# Power_section.net
KiCad netlist of a schematic drawn in Altium Designer
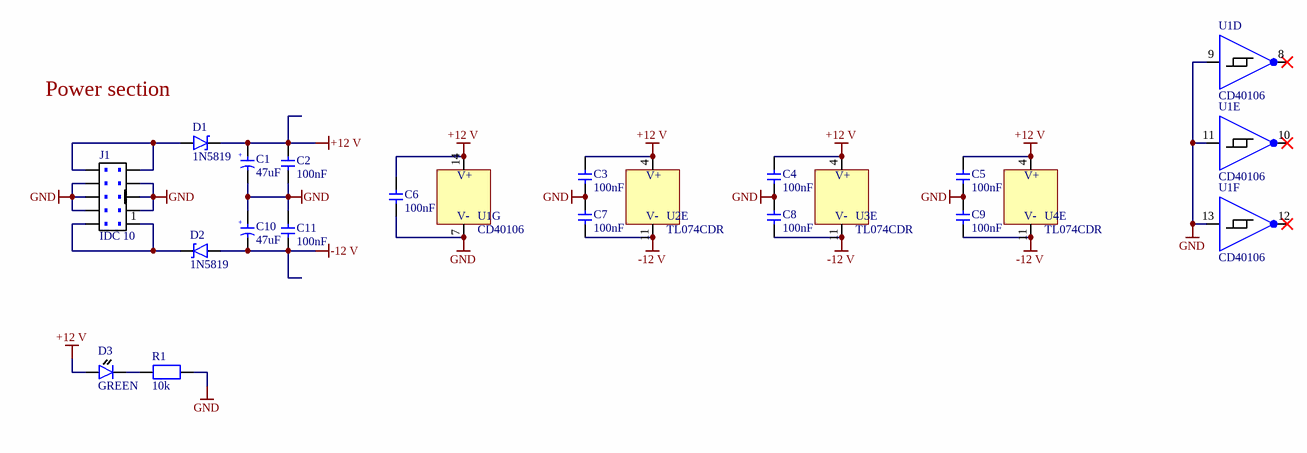
[diagram p0: Power section.SchDoc]

(export (version "E")
  (design (tool "Eeschema 10.0.6"))
  (components
    (comp (ref "C1")
      (value "47uF")
      (footprint "Cap electrolytic THT 5mm")
      (description "THT Electrolytic Capacitor 5 mm Diameter")
      (fields (field (name "Comment") "CAP"))
      (libsource (lib "Generic components") (part "Capacitor Electr THT 5mm"))
    )
    (comp (ref "C2")
      (value "100nF")
      (footprint "Cap SMD 0805")
      (description "SMD Capacitor Non-Polarised 0805 Package")
      (fields (field (name "Comment") "CAP"))
      (libsource (lib "Generic components") (part "Capacitor SMD 0805"))
    )
    (comp (ref "C3")
      (value "100nF")
      (footprint "Cap SMD 0805")
      (description "SMD Capacitor Non-Polarised 0805 Package")
      (fields (field (name "Comment") "CAP"))
      (libsource (lib "Generic components") (part "Capacitor SMD 0805"))
    )
    (comp (ref "C4")
      (value "100nF")
      (footprint "Cap SMD 0805")
      (description "SMD Capacitor Non-Polarised 0805 Package")
      (fields (field (name "Comment") "CAP"))
      (libsource (lib "Generic components") (part "Capacitor SMD 0805"))
    )
    (comp (ref "C5")
      (value "100nF")
      (footprint "Cap SMD 0805")
      (description "SMD Capacitor Non-Polarised 0805 Package")
      (fields (field (name "Comment") "CAP"))
      (libsource (lib "Generic components") (part "Capacitor SMD 0805"))
    )
    (comp (ref "C6")
      (value "100nF")
      (footprint "Cap SMD 0805")
      (description "SMD Capacitor Non-Polarised 0805 Package")
      (fields (field (name "Comment") "CAP"))
      (libsource (lib "Generic components") (part "Capacitor SMD 0805"))
    )
    (comp (ref "C7")
      (value "100nF")
      (footprint "Cap SMD 0805")
      (description "SMD Capacitor Non-Polarised 0805 Package")
      (fields (field (name "Comment") "CAP"))
      (libsource (lib "Generic components") (part "Capacitor SMD 0805"))
    )
    (comp (ref "C8")
      (value "100nF")
      (footprint "Cap SMD 0805")
      (description "SMD Capacitor Non-Polarised 0805 Package")
      (fields (field (name "Comment") "CAP"))
      (libsource (lib "Generic components") (part "Capacitor SMD 0805"))
    )
    (comp (ref "C9")
      (value "100nF")
      (footprint "Cap SMD 0805")
      (description "SMD Capacitor Non-Polarised 0805 Package")
      (fields (field (name "Comment") "CAP"))
      (libsource (lib "Generic components") (part "Capacitor SMD 0805"))
    )
    (comp (ref "C10")
      (value "47uF")
      (footprint "Cap electrolytic THT 5mm")
      (description "THT Electrolytic Capacitor 5 mm Diameter")
      (fields (field (name "Comment") "CAP"))
      (libsource (lib "Generic components") (part "Capacitor Electr THT 5mm"))
    )
    (comp (ref "C11")
      (value "100nF")
      (footprint "Cap SMD 0805")
      (description "SMD Capacitor Non-Polarised 0805 Package")
      (fields (field (name "Comment") "CAP"))
      (libsource (lib "Generic components") (part "Capacitor SMD 0805"))
    )
    (comp (ref "D1")
      (value "SCHOTTKY")
      (footprint "Diode THT 10 mm")
      (description "Generic THT Axial Schottky Diode 10 mm Pitch")
      (fields (field (name "MODEL") "1N5819"))
      (libsource (lib "Diodes") (part "Schottky Diode THT"))
    )
    (comp (ref "D2")
      (value "SCHOTTKY")
      (footprint "Diode THT 10 mm")
      (description "Generic THT Axial Schottky Diode 10 mm Pitch")
      (fields (field (name "MODEL") "1N5819"))
      (libsource (lib "Diodes") (part "Schottky Diode THT"))
    )
    (comp (ref "D3")
      (value "LED")
      (footprint "LED SMD 0805")
      (description "SMD LED Diode 0805 Package")
      (fields (field (name "COLOR") "GREEN"))
      (libsource (lib "Opto") (part "LED SMD"))
    )
    (comp (ref "J1")
      (value "IDC 10")
      (footprint "IDC 10 PIN")
      (description "10 Pin IDC Connector")
      (libsource (lib "Connectors") (part "IDC 10 pin"))
    )
    (comp (ref "R1")
      (value "10k")
      (footprint "Resistor SMD 0805")
      (description "SMD Resistor 0805 package")
      (fields (field (name "Comment") "RES"))
      (libsource (lib "Generic components") (part "Resistor SMD 0805"))
    )
    (comp (ref "U1")
      (value "CD40106")
      (footprint "DIP-14 socket")
      (description "CD40106 Hex Schmitt Trigger Inverter DIP-14 Package")
      (libsource (lib "ICs") (part "CD40106 DIP-14"))
    )
    (comp (ref "U2")
      (value "TL074CDR")
      (footprint "SOIC14")
      (description "TL074CDR Quad Op-Amp SOIC14 Package")
      (libsource (lib "OpAmps") (part "TL074CDR SOIC14"))
    )
    (comp (ref "U3")
      (value "TL074CDR")
      (footprint "SOIC14")
      (description "TL074CDR Quad Op-Amp SOIC14 Package")
      (libsource (lib "OpAmps") (part "TL074CDR SOIC14"))
    )
    (comp (ref "U4")
      (value "TL074CDR")
      (footprint "SOIC14")
      (description "TL074CDR Quad Op-Amp SOIC14 Package")
      (libsource (lib "OpAmps") (part "TL074CDR SOIC14"))
    )
  )
  (nets
    (net (code "1") (name "+12 V") (class "Default")
      (node (ref "C1") (pin "2") (pintype "passive"))
      (node (ref "C2") (pin "2") (pintype "passive"))
      (node (ref "C3") (pin "2") (pintype "passive"))
      (node (ref "C4") (pin "2") (pintype "passive"))
      (node (ref "C5") (pin "2") (pintype "passive"))
      (node (ref "C6") (pin "2") (pintype "passive"))
      (node (ref "D1") (pin "2") (pintype "passive"))
      (node (ref "D3") (pin "1") (pintype "passive"))
      (node (ref "U1") (pin "14") (pintype "passive"))
      (node (ref "U2") (pin "4") (pintype "passive"))
      (node (ref "U3") (pin "4") (pintype "passive"))
      (node (ref "U4") (pin "4") (pintype "passive"))
    )
    (net (code "2") (name "-12 V") (class "Default")
      (node (ref "C10") (pin "1") (pintype "passive"))
      (node (ref "C11") (pin "1") (pintype "passive"))
      (node (ref "C7") (pin "1") (pintype "passive"))
      (node (ref "C8") (pin "1") (pintype "passive"))
      (node (ref "C9") (pin "1") (pintype "passive"))
      (node (ref "D2") (pin "1") (pintype "passive"))
      (node (ref "U2") (pin "11") (pintype "passive"))
      (node (ref "U3") (pin "11") (pintype "passive"))
      (node (ref "U4") (pin "11") (pintype "passive"))
    )
    (net (code "3") (name "GND") (class "Default")
      (node (ref "C1") (pin "1") (pintype "passive"))
      (node (ref "C10") (pin "2") (pintype "passive"))
      (node (ref "C11") (pin "2") (pintype "passive"))
      (node (ref "C2") (pin "1") (pintype "passive"))
      (node (ref "C3") (pin "1") (pintype "passive"))
      (node (ref "C4") (pin "1") (pintype "passive"))
      (node (ref "C5") (pin "1") (pintype "passive"))
      (node (ref "C6") (pin "1") (pintype "passive"))
      (node (ref "C7") (pin "2") (pintype "passive"))
      (node (ref "C8") (pin "2") (pintype "passive"))
      (node (ref "C9") (pin "2") (pintype "passive"))
      (node (ref "J1") (pin "3") (pintype "passive"))
      (node (ref "J1") (pin "4") (pintype "passive"))
      (node (ref "J1") (pin "5") (pintype "passive"))
      (node (ref "J1") (pin "6") (pintype "passive"))
      (node (ref "J1") (pin "7") (pintype "passive"))
      (node (ref "J1") (pin "8") (pintype "passive"))
      (node (ref "R1") (pin "2") (pintype "passive"))
      (node (ref "U1") (pin "11") (pintype "passive"))
      (node (ref "U1") (pin "13") (pintype "passive"))
      (node (ref "U1") (pin "7") (pintype "passive"))
      (node (ref "U1") (pin "9") (pintype "passive"))
    )
    (net (code "4") (name "Net-(D1-Pad1)") (class "Default")
      (node (ref "D1") (pin "1") (pintype "passive"))
      (node (ref "J1") (pin "10") (pintype "passive"))
      (node (ref "J1") (pin "9") (pintype "passive"))
    )
    (net (code "5") (name "Net-(D2-Pad2)") (class "Default")
      (node (ref "D2") (pin "2") (pintype "passive"))
      (node (ref "J1") (pin "1") (pintype "passive"))
      (node (ref "J1") (pin "2") (pintype "passive"))
    )
    (net (code "6") (name "Net-(D3-Pad2)") (class "Default")
      (node (ref "D3") (pin "2") (pintype "passive"))
      (node (ref "R1") (pin "1") (pintype "passive"))
    )
    (net (code "7") (name "unconnected-(U1-Pad8)") (class "Default")
      (node (ref "U1") (pin "8") (pintype "passive+no_connect"))
    )
    (net (code "8") (name "unconnected-(U1-Pad10)") (class "Default")
      (node (ref "U1") (pin "10") (pintype "passive+no_connect"))
    )
    (net (code "9") (name "unconnected-(U1-Pad12)") (class "Default")
      (node (ref "U1") (pin "12") (pintype "passive+no_connect"))
    )
  )
)
